# mppt.net
KiCad netlist of a schematic drawn in Altium Designer
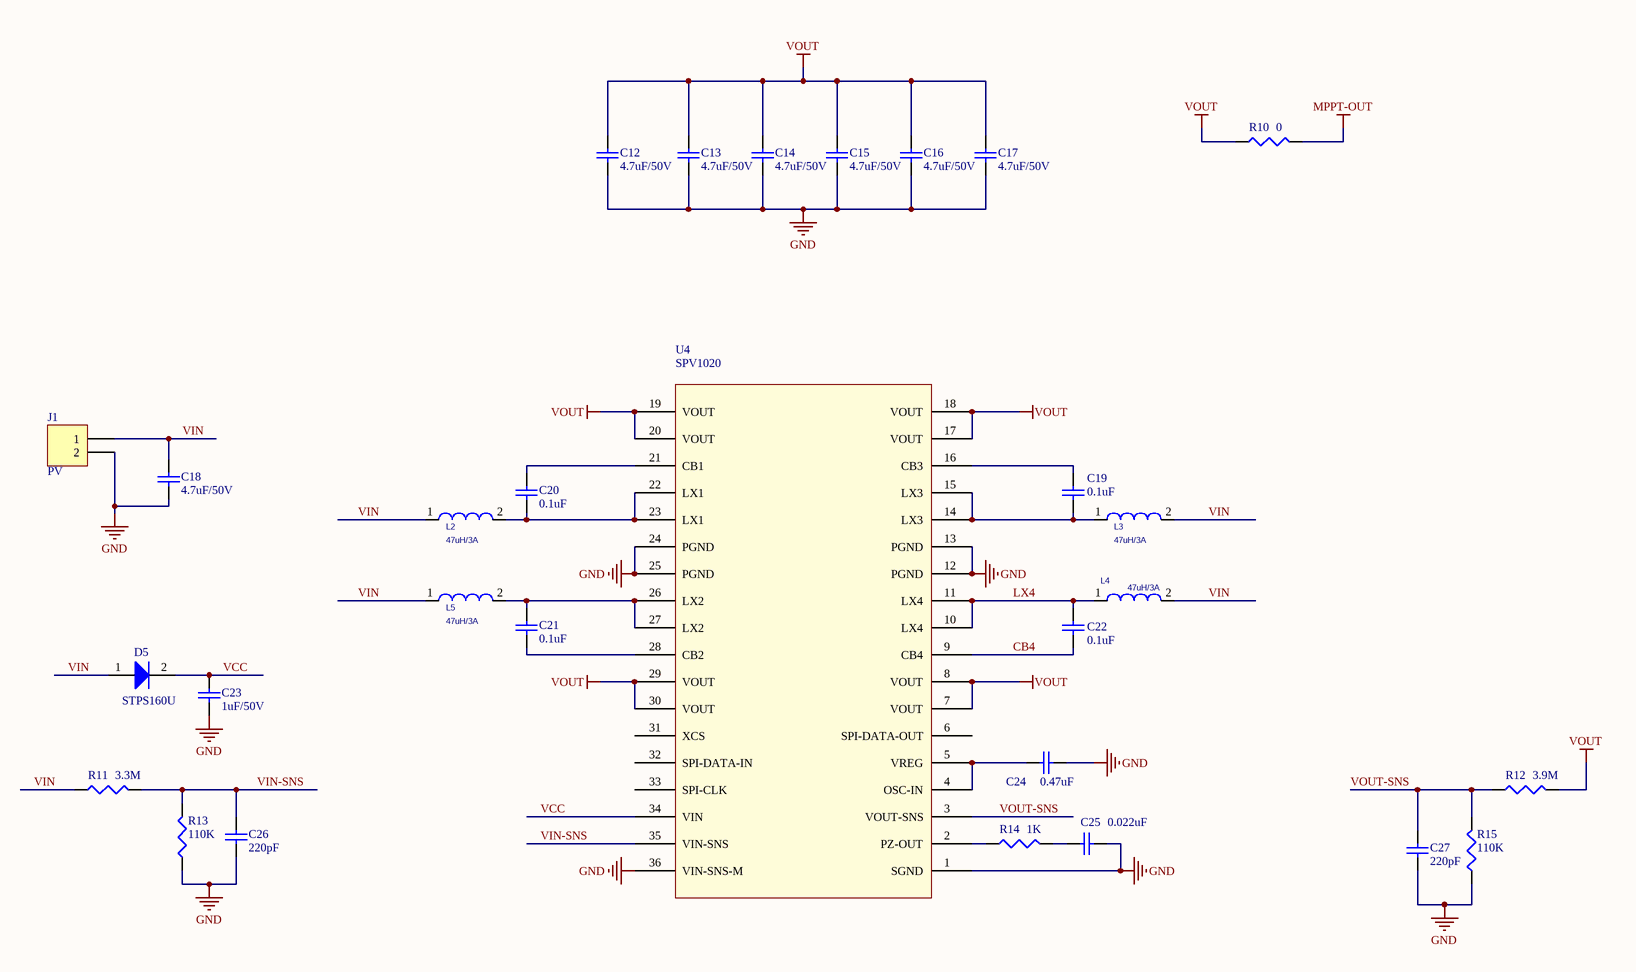
[diagram p0: mppt.SchDoc]

(export (version "E")
  (design (tool "Eeschema 10.0.6"))
  (components
    (comp (ref "C12")
      (value "4.7uF/50V")
      (footprint "1812")
      (description "Capacitor")
      (fields (field (name "PUBLISHER") "Altium Limited"))
      (libsource (lib "Miscellaneous Devices") (part "Cap"))
    )
    (comp (ref "C13")
      (value "4.7uF/50V")
      (footprint "1812")
      (description "Capacitor")
      (fields (field (name "PUBLISHER") "Altium Limited"))
      (libsource (lib "Miscellaneous Devices") (part "Cap"))
    )
    (comp (ref "C14")
      (value "4.7uF/50V")
      (footprint "1812")
      (description "Capacitor")
      (fields (field (name "PUBLISHER") "Altium Limited"))
      (libsource (lib "Miscellaneous Devices") (part "Cap"))
    )
    (comp (ref "C15")
      (value "4.7uF/50V")
      (footprint "1812")
      (description "Capacitor")
      (fields (field (name "PUBLISHER") "Altium Limited"))
      (libsource (lib "Miscellaneous Devices") (part "Cap"))
    )
    (comp (ref "C16")
      (value "4.7uF/50V")
      (footprint "1812")
      (description "Capacitor")
      (fields (field (name "PUBLISHER") "Altium Limited"))
      (libsource (lib "Miscellaneous Devices") (part "Cap"))
    )
    (comp (ref "C17")
      (value "4.7uF/50V")
      (footprint "1812")
      (description "Capacitor")
      (fields (field (name "PUBLISHER") "Altium Limited"))
      (libsource (lib "Miscellaneous Devices") (part "Cap"))
    )
    (comp (ref "C18")
      (value "4.7uF/50V")
      (footprint "1812")
      (description "Capacitor")
      (fields (field (name "PUBLISHER") "Altium Limited"))
      (libsource (lib "Miscellaneous Devices") (part "Cap"))
    )
    (comp (ref "C19")
      (value "0.1uF")
      (footprint "0603")
      (description "Capacitor")
      (fields (field (name "PUBLISHER") "Altium Limited"))
      (libsource (lib "Miscellaneous Devices") (part "Cap"))
    )
    (comp (ref "C20")
      (value "0.1uF")
      (footprint "0603")
      (description "Capacitor")
      (fields (field (name "PUBLISHER") "Altium Limited"))
      (libsource (lib "Miscellaneous Devices") (part "Cap"))
    )
    (comp (ref "C21")
      (value "0.1uF")
      (footprint "0603")
      (description "Capacitor")
      (fields (field (name "PUBLISHER") "Altium Limited"))
      (libsource (lib "Miscellaneous Devices") (part "Cap"))
    )
    (comp (ref "C22")
      (value "0.1uF")
      (footprint "0603")
      (description "Capacitor")
      (fields (field (name "PUBLISHER") "Altium Limited"))
      (libsource (lib "Miscellaneous Devices") (part "Cap"))
    )
    (comp (ref "C23")
      (value "1uF/50V")
      (footprint "1210")
      (description "Capacitor")
      (fields (field (name "PUBLISHER") "Altium Limited"))
      (libsource (lib "Miscellaneous Devices") (part "Cap"))
    )
    (comp (ref "C24")
      (value "0.47uF")
      (footprint "0603")
      (description "Capacitor")
      (fields (field (name "PUBLISHER") "Altium Limited"))
      (libsource (lib "Miscellaneous Devices") (part "Cap"))
    )
    (comp (ref "C25")
      (value "0.022uF")
      (footprint "0603")
      (description "Capacitor")
      (fields (field (name "PUBLISHER") "Altium Limited"))
      (libsource (lib "Miscellaneous Devices") (part "Cap"))
    )
    (comp (ref "C26")
      (value "220pF")
      (footprint "0603")
      (description "Capacitor")
      (fields (field (name "PUBLISHER") "Altium Limited"))
      (libsource (lib "Miscellaneous Devices") (part "Cap"))
    )
    (comp (ref "C27")
      (value "220pF")
      (footprint "0603")
      (description "Capacitor")
      (fields (field (name "PUBLISHER") "Altium Limited"))
      (libsource (lib "Miscellaneous Devices") (part "Cap"))
    )
    (comp (ref "D5")
      (value "STPS160U")
      (footprint "B320A")
      (description "Default Diode")
      (fields (field (name "PUBLISHER") "Altium Limited"))
      (libsource (lib "Miscellaneous Devices") (part "Diode"))
    )
    (comp (ref "J1")
      (value "PV")
      (footprint "T-2PIN")
      (description "Header, 2-Pin")
      (fields (field (name "PUBLISHER") "Altium Limited"))
      (libsource (lib "Miscellaneous Connectors") (part "Header 2"))
    )
    (comp (ref "L2")
      (value "47uH/3A")
      (footprint "IND-47UH-3A")
      (fields (field (name "PART NUMBER") "SH00000AJ00"))
      (libsource (lib "*") (part "4.7UH_CDH2D09BNP-4R7MC_0.7A_20%"))
    )
    (comp (ref "L3")
      (value "47uH/3A")
      (footprint "IND-47UH-3A")
      (fields (field (name "PART NUMBER") "SH00000AJ00"))
      (libsource (lib "*") (part "4.7UH_CDH2D09BNP-4R7MC_0.7A_20%"))
    )
    (comp (ref "L4")
      (value "47uH/3A")
      (footprint "IND-47UH-3A")
      (fields (field (name "PART NUMBER") "SH00000AJ00"))
      (libsource (lib "*") (part "4.7UH_CDH2D09BNP-4R7MC_0.7A_20%"))
    )
    (comp (ref "L5")
      (value "47uH/3A")
      (footprint "IND-47UH-3A")
      (fields (field (name "PART NUMBER") "SH00000AJ00"))
      (libsource (lib "*") (part "4.7UH_CDH2D09BNP-4R7MC_0.7A_20%"))
    )
    (comp (ref "R10")
      (value "0")
      (footprint "BREAK")
      (description "Resistor")
      (fields (field (name "PUBLISHER") "Altium Limited"))
      (libsource (lib "Miscellaneous Devices") (part "Res3"))
    )
    (comp (ref "R11")
      (value "3.3M")
      (footprint "0603")
      (description "Resistor")
      (fields (field (name "PUBLISHER") "Altium Limited"))
      (libsource (lib "Miscellaneous Devices") (part "Res3"))
    )
    (comp (ref "R12")
      (value "3.9M")
      (footprint "0603")
      (description "Resistor")
      (fields (field (name "PUBLISHER") "Altium Limited"))
      (libsource (lib "Miscellaneous Devices") (part "Res3"))
    )
    (comp (ref "R13")
      (value "110K")
      (footprint "0603")
      (description "Resistor")
      (fields (field (name "PUBLISHER") "Altium Limited"))
      (libsource (lib "Miscellaneous Devices") (part "Res3"))
    )
    (comp (ref "R14")
      (value "1K")
      (footprint "0603")
      (description "Resistor")
      (fields (field (name "PUBLISHER") "Altium Limited"))
      (libsource (lib "Miscellaneous Devices") (part "Res3"))
    )
    (comp (ref "R15")
      (value "110K")
      (footprint "0603")
      (description "Resistor")
      (fields (field (name "PUBLISHER") "Altium Limited"))
      (libsource (lib "Miscellaneous Devices") (part "Res3"))
    )
    (comp (ref "U4") (value "SPV1020") (footprint "POWERSSOP36") (libsource (lib "Schlib") (part "SPV1020")))
  )
  (nets
    (net (code "1") (name "/CB4") (class "Default")
      (node (ref "C22") (pin "1") (pinfunction "1_1") (pintype "passive"))
      (node (ref "U4") (pin "9") (pinfunction "CB4_9") (pintype "passive"))
    )
    (net (code "2") (name "/LX4") (class "Default")
      (node (ref "C22") (pin "2") (pinfunction "2_2") (pintype "passive"))
      (node (ref "L4") (pin "1") (pinfunction "1_1") (pintype "passive"))
      (node (ref "U4") (pin "10") (pinfunction "LX4_10") (pintype "passive"))
      (node (ref "U4") (pin "11") (pinfunction "LX4_11") (pintype "passive"))
    )
    (net (code "3") (name "/VCC") (class "Default")
      (node (ref "C23") (pin "2") (pinfunction "2_2") (pintype "passive"))
      (node (ref "D5") (pin "2") (pinfunction "K_2") (pintype "passive"))
      (node (ref "U4") (pin "34") (pinfunction "VIN_34") (pintype "passive"))
    )
    (net (code "4") (name "/VIN") (class "Default")
      (node (ref "C18") (pin "2") (pinfunction "2_2") (pintype "passive"))
      (node (ref "D5") (pin "1") (pinfunction "A_1") (pintype "passive"))
      (node (ref "J1") (pin "1") (pinfunction "1_1") (pintype "passive"))
      (node (ref "L2") (pin "1") (pinfunction "1_1") (pintype "passive"))
      (node (ref "L3") (pin "2") (pinfunction "2_2") (pintype "passive"))
      (node (ref "L4") (pin "2") (pinfunction "2_2") (pintype "passive"))
      (node (ref "L5") (pin "1") (pinfunction "1_1") (pintype "passive"))
      (node (ref "R11") (pin "1") (pinfunction "1_1") (pintype "passive"))
    )
    (net (code "5") (name "/VIN-SNS") (class "Default")
      (node (ref "C26") (pin "2") (pinfunction "2_2") (pintype "passive"))
      (node (ref "R11") (pin "2") (pinfunction "2_2") (pintype "passive"))
      (node (ref "R13") (pin "2") (pinfunction "2_2") (pintype "passive"))
      (node (ref "U4") (pin "35") (pinfunction "VIN-SNS_35") (pintype "passive"))
    )
    (net (code "6") (name "/VOUT-SNS") (class "Default")
      (node (ref "C27") (pin "2") (pinfunction "2_2") (pintype "passive"))
      (node (ref "R12") (pin "1") (pinfunction "1_1") (pintype "passive"))
      (node (ref "R15") (pin "2") (pinfunction "2_2") (pintype "passive"))
      (node (ref "U4") (pin "3") (pinfunction "VOUT-SNS_3") (pintype "passive"))
    )
    (net (code "7") (name "GND") (class "Default")
      (node (ref "C12") (pin "1") (pinfunction "1_1") (pintype "passive"))
      (node (ref "C13") (pin "1") (pinfunction "1_1") (pintype "passive"))
      (node (ref "C14") (pin "1") (pinfunction "1_1") (pintype "passive"))
      (node (ref "C15") (pin "1") (pinfunction "1_1") (pintype "passive"))
      (node (ref "C16") (pin "1") (pinfunction "1_1") (pintype "passive"))
      (node (ref "C17") (pin "1") (pinfunction "1_1") (pintype "passive"))
      (node (ref "C18") (pin "1") (pinfunction "1_1") (pintype "passive"))
      (node (ref "C23") (pin "1") (pinfunction "1_1") (pintype "passive"))
      (node (ref "C24") (pin "2") (pinfunction "2_2") (pintype "passive"))
      (node (ref "C25") (pin "2") (pinfunction "2_2") (pintype "passive"))
      (node (ref "C26") (pin "1") (pinfunction "1_1") (pintype "passive"))
      (node (ref "C27") (pin "1") (pinfunction "1_1") (pintype "passive"))
      (node (ref "J1") (pin "2") (pinfunction "2_2") (pintype "passive"))
      (node (ref "R13") (pin "1") (pinfunction "1_1") (pintype "passive"))
      (node (ref "R15") (pin "1") (pinfunction "1_1") (pintype "passive"))
      (node (ref "U4") (pin "1") (pinfunction "SGND_1") (pintype "passive"))
      (node (ref "U4") (pin "12") (pinfunction "PGND_12") (pintype "passive"))
      (node (ref "U4") (pin "13") (pinfunction "PGND_13") (pintype "passive"))
      (node (ref "U4") (pin "24") (pinfunction "PGND_24") (pintype "passive"))
      (node (ref "U4") (pin "25") (pinfunction "PGND_25") (pintype "passive"))
      (node (ref "U4") (pin "36") (pinfunction "VIN-SNS-M_36") (pintype "passive"))
    )
    (net (code "8") (name "MPPT-OUT") (class "Default")
      (node (ref "R10") (pin "2") (pinfunction "2_2") (pintype "passive"))
    )
    (net (code "9") (name "Net-(C19-Pad1)") (class "Default")
      (node (ref "C19") (pin "1") (pinfunction "1_1") (pintype "passive"))
      (node (ref "L3") (pin "1") (pinfunction "1_1") (pintype "passive"))
      (node (ref "U4") (pin "14") (pinfunction "LX3_14") (pintype "passive"))
      (node (ref "U4") (pin "15") (pinfunction "LX3_15") (pintype "passive"))
    )
    (net (code "10") (name "Net-(C20-Pad1)") (class "Default")
      (node (ref "C20") (pin "1") (pinfunction "1_1") (pintype "passive"))
      (node (ref "L2") (pin "2") (pinfunction "2_2") (pintype "passive"))
      (node (ref "U4") (pin "22") (pinfunction "LX1_22") (pintype "passive"))
      (node (ref "U4") (pin "23") (pinfunction "LX1_23") (pintype "passive"))
    )
    (net (code "11") (name "Net-(C21-Pad2)") (class "Default")
      (node (ref "C21") (pin "2") (pinfunction "2_2") (pintype "passive"))
      (node (ref "L5") (pin "2") (pinfunction "2_2") (pintype "passive"))
      (node (ref "U4") (pin "26") (pinfunction "LX2_26") (pintype "passive"))
      (node (ref "U4") (pin "27") (pinfunction "LX2_27") (pintype "passive"))
    )
    (net (code "12") (name "Net-(C25-Pad1)") (class "Default")
      (node (ref "C25") (pin "1") (pinfunction "1_1") (pintype "passive"))
      (node (ref "R14") (pin "2") (pinfunction "2_2") (pintype "passive"))
    )
    (net (code "13") (name "Net-(U4-CB1)") (class "Default")
      (node (ref "C20") (pin "2") (pinfunction "2_2") (pintype "passive"))
      (node (ref "U4") (pin "21") (pinfunction "CB1_21") (pintype "passive"))
    )
    (net (code "14") (name "Net-(U4-CB2)") (class "Default")
      (node (ref "C21") (pin "1") (pinfunction "1_1") (pintype "passive"))
      (node (ref "U4") (pin "28") (pinfunction "CB2_28") (pintype "passive"))
    )
    (net (code "15") (name "Net-(U4-CB3)") (class "Default")
      (node (ref "C19") (pin "2") (pinfunction "2_2") (pintype "passive"))
      (node (ref "U4") (pin "16") (pinfunction "CB3_16") (pintype "passive"))
    )
    (net (code "16") (name "Net-(U4-OSC-IN)") (class "Default")
      (node (ref "C24") (pin "1") (pinfunction "1_1") (pintype "passive"))
      (node (ref "U4") (pin "4") (pinfunction "OSC-IN_4") (pintype "passive"))
      (node (ref "U4") (pin "5") (pinfunction "VREG_5") (pintype "passive"))
    )
    (net (code "17") (name "Net-(U4-PZ-OUT)") (class "Default")
      (node (ref "R14") (pin "1") (pinfunction "1_1") (pintype "passive"))
      (node (ref "U4") (pin "2") (pinfunction "PZ-OUT_2") (pintype "passive"))
    )
    (net (code "18") (name "VOUT") (class "Default")
      (node (ref "C12") (pin "2") (pinfunction "2_2") (pintype "passive"))
      (node (ref "C13") (pin "2") (pinfunction "2_2") (pintype "passive"))
      (node (ref "C14") (pin "2") (pinfunction "2_2") (pintype "passive"))
      (node (ref "C15") (pin "2") (pinfunction "2_2") (pintype "passive"))
      (node (ref "C16") (pin "2") (pinfunction "2_2") (pintype "passive"))
      (node (ref "C17") (pin "2") (pinfunction "2_2") (pintype "passive"))
      (node (ref "R10") (pin "1") (pinfunction "1_1") (pintype "passive"))
      (node (ref "R12") (pin "2") (pinfunction "2_2") (pintype "passive"))
      (node (ref "U4") (pin "17") (pinfunction "VOUT_17") (pintype "passive"))
      (node (ref "U4") (pin "18") (pinfunction "VOUT_18") (pintype "passive"))
      (node (ref "U4") (pin "19") (pinfunction "VOUT_19") (pintype "passive"))
      (node (ref "U4") (pin "20") (pinfunction "VOUT_20") (pintype "passive"))
      (node (ref "U4") (pin "29") (pinfunction "VOUT_29") (pintype "passive"))
      (node (ref "U4") (pin "30") (pinfunction "VOUT_30") (pintype "passive"))
      (node (ref "U4") (pin "7") (pinfunction "VOUT_7") (pintype "passive"))
      (node (ref "U4") (pin "8") (pinfunction "VOUT_8") (pintype "passive"))
    )
    (net (code "19") (name "unconnected-(U4-SPI-CLK-Pad33)") (class "Default")
      (node (ref "U4") (pin "33") (pinfunction "SPI-CLK_33") (pintype "passive"))
    )
    (net (code "20") (name "unconnected-(U4-SPI-DATA-IN-Pad32)") (class "Default")
      (node (ref "U4") (pin "32") (pinfunction "SPI-DATA-IN_32") (pintype "passive"))
    )
    (net (code "21") (name "unconnected-(U4-SPI-DATA-OUT-Pad6)") (class "Default")
      (node (ref "U4") (pin "6") (pinfunction "SPI-DATA-OUT_6") (pintype "passive"))
    )
    (net (code "22") (name "unconnected-(U4-XCS-Pad31)") (class "Default")
      (node (ref "U4") (pin "31") (pinfunction "XCS_31") (pintype "passive"))
    )
  )
)
